# 3DS_Cartridge.net
KiCad netlist of a schematic drawn in EAGLE
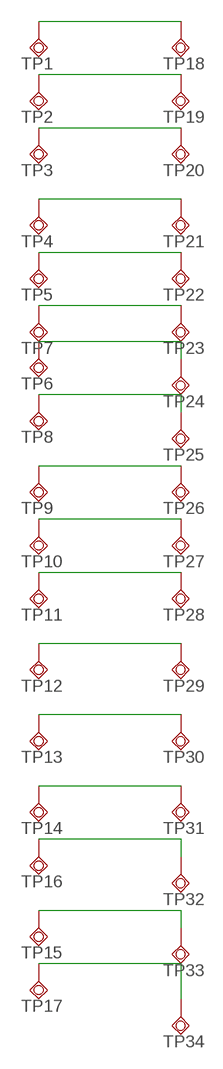
[diagram p0: schematic, sheet 1]

(export (version "E")
  (design (tool "Eeschema 10.0.6"))
  (components
    (comp (ref "TP1")
      (value "TPSQTP12SQ")
      (footprint "eagle-import:TP12SQ")
      (libsource (lib "eagle-import") (part "TPSQTP12SQ"))
    )
    (comp (ref "TP2")
      (value "TPSQTP12SQ")
      (footprint "eagle-import:TP12SQ")
      (libsource (lib "eagle-import") (part "TPSQTP12SQ"))
    )
    (comp (ref "TP3")
      (value "TPSQTP12SQ")
      (footprint "eagle-import:TP12SQ")
      (libsource (lib "eagle-import") (part "TPSQTP12SQ"))
    )
    (comp (ref "TP4")
      (value "TPSQTP12SQ")
      (footprint "eagle-import:TP12SQ")
      (libsource (lib "eagle-import") (part "TPSQTP12SQ"))
    )
    (comp (ref "TP5")
      (value "TPSQTP12SQ")
      (footprint "eagle-import:TP12SQ")
      (libsource (lib "eagle-import") (part "TPSQTP12SQ"))
    )
    (comp (ref "TP6")
      (value "TPSQTP12SQ")
      (footprint "eagle-import:TP12SQ")
      (libsource (lib "eagle-import") (part "TPSQTP12SQ"))
    )
    (comp (ref "TP7")
      (value "TPSQTP12SQ")
      (footprint "eagle-import:TP12SQ")
      (libsource (lib "eagle-import") (part "TPSQTP12SQ"))
    )
    (comp (ref "TP8")
      (value "TPSQTP12SQ")
      (footprint "eagle-import:TP12SQ")
      (libsource (lib "eagle-import") (part "TPSQTP12SQ"))
    )
    (comp (ref "TP9")
      (value "TPSQTP12SQ")
      (footprint "eagle-import:TP12SQ")
      (libsource (lib "eagle-import") (part "TPSQTP12SQ"))
    )
    (comp (ref "TP10")
      (value "TPSQTP12SQ")
      (footprint "eagle-import:TP12SQ")
      (libsource (lib "eagle-import") (part "TPSQTP12SQ"))
    )
    (comp (ref "TP11")
      (value "TPSQTP12SQ")
      (footprint "eagle-import:TP12SQ")
      (libsource (lib "eagle-import") (part "TPSQTP12SQ"))
    )
    (comp (ref "TP12")
      (value "TPSQTP12SQ")
      (footprint "eagle-import:TP12SQ")
      (libsource (lib "eagle-import") (part "TPSQTP12SQ"))
    )
    (comp (ref "TP13")
      (value "TPSQTP12SQ")
      (footprint "eagle-import:TP12SQ")
      (libsource (lib "eagle-import") (part "TPSQTP12SQ"))
    )
    (comp (ref "TP14")
      (value "TPSQTP12SQ")
      (footprint "eagle-import:TP12SQ")
      (libsource (lib "eagle-import") (part "TPSQTP12SQ"))
    )
    (comp (ref "TP15")
      (value "TPSQTP12SQ")
      (footprint "eagle-import:TP12SQ")
      (libsource (lib "eagle-import") (part "TPSQTP12SQ"))
    )
    (comp (ref "TP16")
      (value "TPSQTP12SQ")
      (footprint "eagle-import:TP12SQ")
      (libsource (lib "eagle-import") (part "TPSQTP12SQ"))
    )
    (comp (ref "TP17")
      (value "TPSQTP12SQ")
      (footprint "eagle-import:TP12SQ")
      (libsource (lib "eagle-import") (part "TPSQTP12SQ"))
    )
    (comp (ref "TP18")
      (value "TPSQTP12SQ")
      (footprint "eagle-import:TP12SQ")
      (libsource (lib "eagle-import") (part "TPSQTP12SQ"))
    )
    (comp (ref "TP19")
      (value "TPSQTP12SQ")
      (footprint "eagle-import:TP12SQ")
      (libsource (lib "eagle-import") (part "TPSQTP12SQ"))
    )
    (comp (ref "TP20")
      (value "TPSQTP12SQ")
      (footprint "eagle-import:TP12SQ")
      (libsource (lib "eagle-import") (part "TPSQTP12SQ"))
    )
    (comp (ref "TP21")
      (value "TPSQTP12SQ")
      (footprint "eagle-import:TP12SQ")
      (libsource (lib "eagle-import") (part "TPSQTP12SQ"))
    )
    (comp (ref "TP22")
      (value "TPSQTP12SQ")
      (footprint "eagle-import:TP12SQ")
      (libsource (lib "eagle-import") (part "TPSQTP12SQ"))
    )
    (comp (ref "TP23")
      (value "TPSQTP12SQ")
      (footprint "eagle-import:TP12SQ")
      (libsource (lib "eagle-import") (part "TPSQTP12SQ"))
    )
    (comp (ref "TP24")
      (value "TPSQTP12SQ")
      (footprint "eagle-import:TP12SQ")
      (libsource (lib "eagle-import") (part "TPSQTP12SQ"))
    )
    (comp (ref "TP25")
      (value "TPSQTP12SQ")
      (footprint "eagle-import:TP12SQ")
      (libsource (lib "eagle-import") (part "TPSQTP12SQ"))
    )
    (comp (ref "TP26")
      (value "TPSQTP12SQ")
      (footprint "eagle-import:TP12SQ")
      (libsource (lib "eagle-import") (part "TPSQTP12SQ"))
    )
    (comp (ref "TP27")
      (value "TPSQTP12SQ")
      (footprint "eagle-import:TP12SQ")
      (libsource (lib "eagle-import") (part "TPSQTP12SQ"))
    )
    (comp (ref "TP28")
      (value "TPSQTP12SQ")
      (footprint "eagle-import:TP12SQ")
      (libsource (lib "eagle-import") (part "TPSQTP12SQ"))
    )
    (comp (ref "TP29")
      (value "TPSQTP12SQ")
      (footprint "eagle-import:TP12SQ")
      (libsource (lib "eagle-import") (part "TPSQTP12SQ"))
    )
    (comp (ref "TP30")
      (value "TPSQTP12SQ")
      (footprint "eagle-import:TP12SQ")
      (libsource (lib "eagle-import") (part "TPSQTP12SQ"))
    )
    (comp (ref "TP31")
      (value "TPSQTP12SQ")
      (footprint "eagle-import:TP12SQ")
      (libsource (lib "eagle-import") (part "TPSQTP12SQ"))
    )
    (comp (ref "TP32")
      (value "TPSQTP12SQ")
      (footprint "eagle-import:TP12SQ")
      (libsource (lib "eagle-import") (part "TPSQTP12SQ"))
    )
    (comp (ref "TP33")
      (value "TPSQTP12SQ")
      (footprint "eagle-import:TP12SQ")
      (libsource (lib "eagle-import") (part "TPSQTP12SQ"))
    )
    (comp (ref "TP34")
      (value "TPSQTP12SQ")
      (footprint "eagle-import:TP12SQ")
      (libsource (lib "eagle-import") (part "TPSQTP12SQ"))
    )
  )
  (nets
    (net (code "1") (name "Net-(TP1-PadTP)") (class "Default")
      (node (ref "TP1") (pin "TP") (pinfunction "TP_TP") (pintype "input"))
      (node (ref "TP18") (pin "TP") (pinfunction "TP_TP") (pintype "input"))
    )
    (net (code "2") (name "Net-(TP10-PadTP)") (class "Default")
      (node (ref "TP10") (pin "TP") (pinfunction "TP_TP") (pintype "input"))
      (node (ref "TP27") (pin "TP") (pinfunction "TP_TP") (pintype "input"))
    )
    (net (code "3") (name "Net-(TP11-PadTP)") (class "Default")
      (node (ref "TP11") (pin "TP") (pinfunction "TP_TP") (pintype "input"))
      (node (ref "TP28") (pin "TP") (pinfunction "TP_TP") (pintype "input"))
    )
    (net (code "4") (name "Net-(TP12-PadTP)") (class "Default")
      (node (ref "TP12") (pin "TP") (pinfunction "TP_TP") (pintype "input"))
      (node (ref "TP29") (pin "TP") (pinfunction "TP_TP") (pintype "input"))
    )
    (net (code "5") (name "Net-(TP13-PadTP)") (class "Default")
      (node (ref "TP13") (pin "TP") (pinfunction "TP_TP") (pintype "input"))
      (node (ref "TP30") (pin "TP") (pinfunction "TP_TP") (pintype "input"))
    )
    (net (code "6") (name "Net-(TP14-PadTP)") (class "Default")
      (node (ref "TP14") (pin "TP") (pinfunction "TP_TP") (pintype "input"))
      (node (ref "TP31") (pin "TP") (pinfunction "TP_TP") (pintype "input"))
    )
    (net (code "7") (name "Net-(TP15-PadTP)") (class "Default")
      (node (ref "TP15") (pin "TP") (pinfunction "TP_TP") (pintype "input"))
      (node (ref "TP33") (pin "TP") (pinfunction "TP_TP") (pintype "input"))
    )
    (net (code "8") (name "Net-(TP16-PadTP)") (class "Default")
      (node (ref "TP16") (pin "TP") (pinfunction "TP_TP") (pintype "input"))
      (node (ref "TP32") (pin "TP") (pinfunction "TP_TP") (pintype "input"))
    )
    (net (code "9") (name "Net-(TP17-PadTP)") (class "Default")
      (node (ref "TP17") (pin "TP") (pinfunction "TP_TP") (pintype "input"))
      (node (ref "TP34") (pin "TP") (pinfunction "TP_TP") (pintype "input"))
    )
    (net (code "10") (name "Net-(TP19-PadTP)") (class "Default")
      (node (ref "TP19") (pin "TP") (pinfunction "TP_TP") (pintype "input"))
      (node (ref "TP2") (pin "TP") (pinfunction "TP_TP") (pintype "input"))
    )
    (net (code "11") (name "Net-(TP20-PadTP)") (class "Default")
      (node (ref "TP20") (pin "TP") (pinfunction "TP_TP") (pintype "input"))
      (node (ref "TP3") (pin "TP") (pinfunction "TP_TP") (pintype "input"))
    )
    (net (code "12") (name "Net-(TP21-PadTP)") (class "Default")
      (node (ref "TP21") (pin "TP") (pinfunction "TP_TP") (pintype "input"))
      (node (ref "TP4") (pin "TP") (pinfunction "TP_TP") (pintype "input"))
    )
    (net (code "13") (name "Net-(TP22-PadTP)") (class "Default")
      (node (ref "TP22") (pin "TP") (pinfunction "TP_TP") (pintype "input"))
      (node (ref "TP5") (pin "TP") (pinfunction "TP_TP") (pintype "input"))
    )
    (net (code "14") (name "Net-(TP23-PadTP)") (class "Default")
      (node (ref "TP23") (pin "TP") (pinfunction "TP_TP") (pintype "input"))
      (node (ref "TP7") (pin "TP") (pinfunction "TP_TP") (pintype "input"))
    )
    (net (code "15") (name "Net-(TP24-PadTP)") (class "Default")
      (node (ref "TP24") (pin "TP") (pinfunction "TP_TP") (pintype "input"))
      (node (ref "TP6") (pin "TP") (pinfunction "TP_TP") (pintype "input"))
    )
    (net (code "16") (name "Net-(TP25-PadTP)") (class "Default")
      (node (ref "TP25") (pin "TP") (pinfunction "TP_TP") (pintype "input"))
      (node (ref "TP8") (pin "TP") (pinfunction "TP_TP") (pintype "input"))
    )
    (net (code "17") (name "Net-(TP26-PadTP)") (class "Default")
      (node (ref "TP26") (pin "TP") (pinfunction "TP_TP") (pintype "input"))
      (node (ref "TP9") (pin "TP") (pinfunction "TP_TP") (pintype "input"))
    )
  )
)
